# AY_Amp.net
KiCad netlist of a schematic drawn in Altium Designer
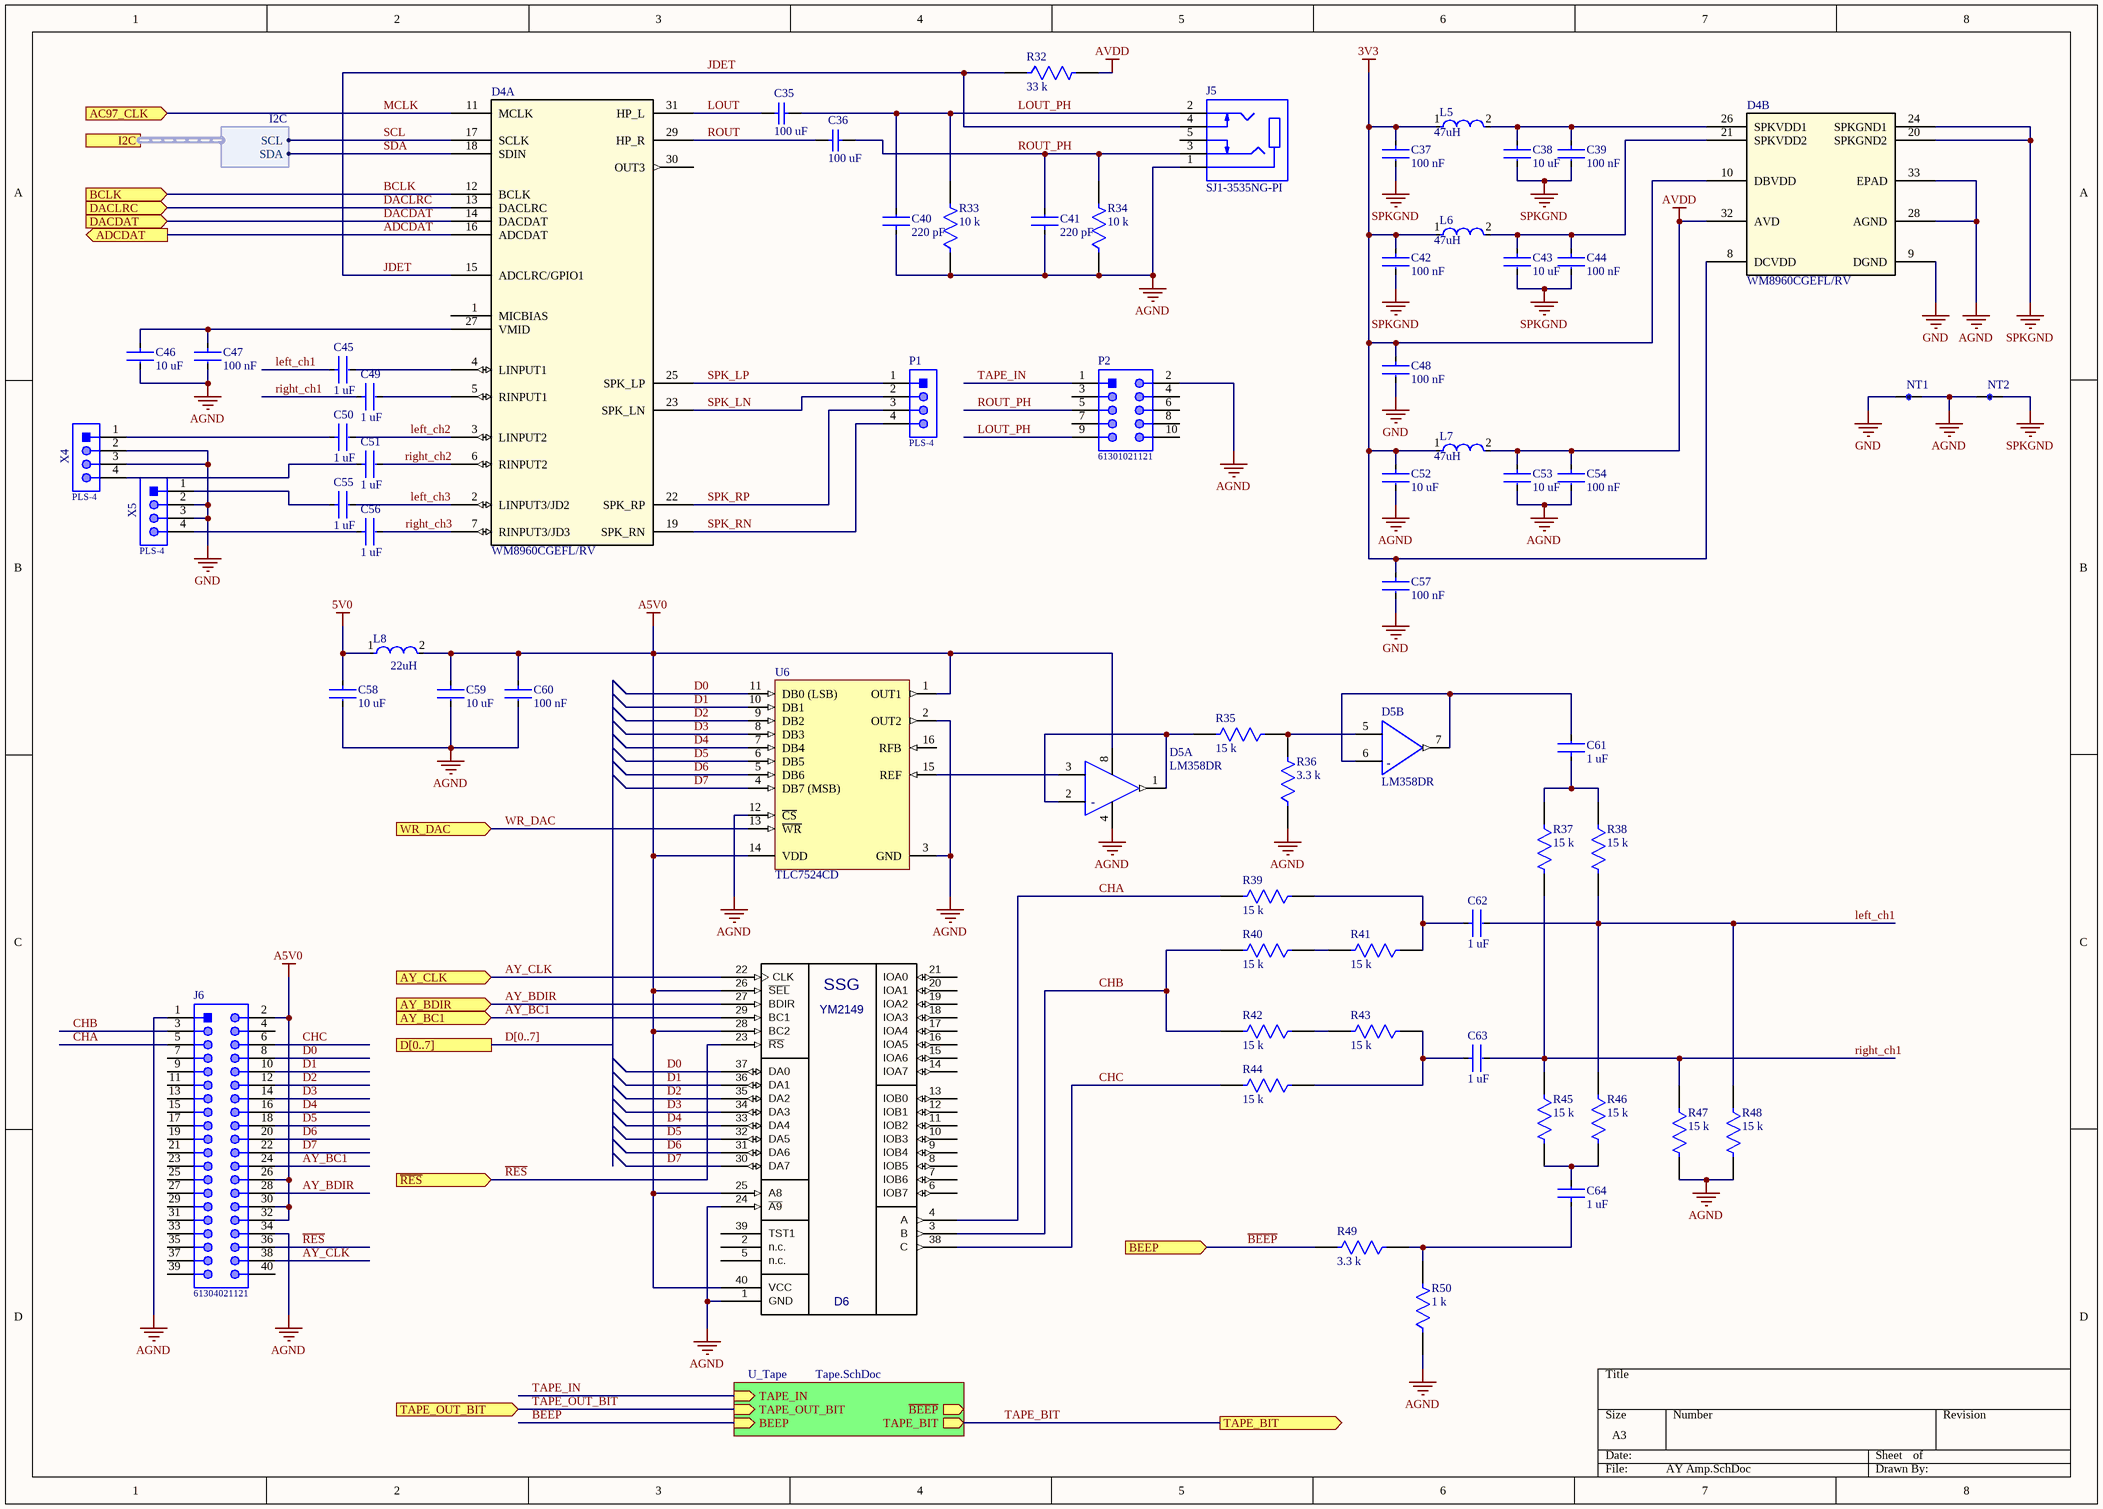
[diagram p0: AY Amp.SchDoc]

(export (version "E")
  (design (tool "Eeschema 10.0.6"))
  (components
    (comp (ref "C35")
      (value "CC1206-100uF")
      (footprint "CAPC3216X190X55ML30T25")
      (description "Chip Capacitor, 100 uF, +/- 20%, 6.3 V, -55 to 85 degC, 1206 (3216 Metric), RoHS, Tape and Reel")
      (fields
        (field (name "CAPACITANCE") "100 uF")
        (field (name "PARTNUMBER") "GRM31CR60J107ME39L")
        (field (name "MANUFACTURER") "Murata")
      )
      (libsource (lib "zxevo") (part "CMP-1662-00011-2"))
    )
    (comp (ref "C36")
      (value "CC1206-100uF")
      (footprint "CAPC3216X190X55ML30T25")
      (description "Chip Capacitor, 100 uF, +/- 20%, 6.3 V, -55 to 85 degC, 1206 (3216 Metric), RoHS, Tape and Reel")
      (fields
        (field (name "CAPACITANCE") "100 uF")
        (field (name "PARTNUMBER") "GRM31CR60J107ME39L")
        (field (name "MANUFACTURER") "Murata")
      )
      (libsource (lib "zxevo") (part "CMP-1662-00011-2"))
    )
    (comp (ref "C37")
      (value "CC0805-1.5pF")
      (footprint "CC0805")
      (description "CL21 Series 0805 1.5pF 50V ±0.25pF Tolerance C0G Multilayer Ceramic Chip Capacitor")
      (fields
        (field (name "MANUFACTURER PART NUMBER") "CL21C1R5CBANNNC")
        (field (name "MANUFACTURER") "Samsung")
        (field (name "CAPACITANCE") "100 nF")
      )
      (libsource (lib "zxevo") (part "CC0805"))
    )
    (comp (ref "C38")
      (value "CC0805-1.5pF")
      (footprint "CC0805")
      (description "CL21 Series 0805 1.5pF 50V ±0.25pF Tolerance C0G Multilayer Ceramic Chip Capacitor")
      (fields
        (field (name "MANUFACTURER PART NUMBER") "CL21C1R5CBANNNC")
        (field (name "MANUFACTURER") "Samsung")
        (field (name "CAPACITANCE") "10 uF")
      )
      (libsource (lib "zxevo") (part "CC0805"))
    )
    (comp (ref "C39")
      (value "CC0805-1.5pF")
      (footprint "CC0805")
      (description "CL21 Series 0805 1.5pF 50V ±0.25pF Tolerance C0G Multilayer Ceramic Chip Capacitor")
      (fields
        (field (name "MANUFACTURER PART NUMBER") "CL21C1R5CBANNNC")
        (field (name "MANUFACTURER") "Samsung")
        (field (name "CAPACITANCE") "100 nF")
      )
      (libsource (lib "zxevo") (part "CC0805"))
    )
    (comp (ref "C40")
      (value "CC0805-1.5pF")
      (footprint "CC0805")
      (description "CL21 Series 0805 1.5pF 50V ±0.25pF Tolerance C0G Multilayer Ceramic Chip Capacitor")
      (fields
        (field (name "MANUFACTURER PART NUMBER") "CL21C1R5CBANNNC")
        (field (name "CAPACITANCE") "220 pF")
        (field (name "MANUFACTURER") "Samsung")
      )
      (libsource (lib "zxevo") (part "CC0805"))
    )
    (comp (ref "C41")
      (value "CC0805-1.5pF")
      (footprint "CC0805")
      (description "CL21 Series 0805 1.5pF 50V ±0.25pF Tolerance C0G Multilayer Ceramic Chip Capacitor")
      (fields
        (field (name "MANUFACTURER PART NUMBER") "CL21C1R5CBANNNC")
        (field (name "CAPACITANCE") "220 pF")
        (field (name "MANUFACTURER") "Samsung")
      )
      (libsource (lib "zxevo") (part "CC0805"))
    )
    (comp (ref "C42")
      (value "CC0805-1.5pF")
      (footprint "CC0805")
      (description "CL21 Series 0805 1.5pF 50V ±0.25pF Tolerance C0G Multilayer Ceramic Chip Capacitor")
      (fields
        (field (name "MANUFACTURER PART NUMBER") "CL21C1R5CBANNNC")
        (field (name "MANUFACTURER") "Samsung")
        (field (name "CAPACITANCE") "100 nF")
      )
      (libsource (lib "zxevo") (part "CC0805"))
    )
    (comp (ref "C43")
      (value "CC0805-1.5pF")
      (footprint "CC0805")
      (description "CL21 Series 0805 1.5pF 50V ±0.25pF Tolerance C0G Multilayer Ceramic Chip Capacitor")
      (fields
        (field (name "MANUFACTURER PART NUMBER") "CL21C1R5CBANNNC")
        (field (name "MANUFACTURER") "Samsung")
        (field (name "CAPACITANCE") "10 uF")
      )
      (libsource (lib "zxevo") (part "CC0805"))
    )
    (comp (ref "C44")
      (value "CC0805-1.5pF")
      (footprint "CC0805")
      (description "CL21 Series 0805 1.5pF 50V ±0.25pF Tolerance C0G Multilayer Ceramic Chip Capacitor")
      (fields
        (field (name "MANUFACTURER PART NUMBER") "CL21C1R5CBANNNC")
        (field (name "MANUFACTURER") "Samsung")
        (field (name "CAPACITANCE") "100 nF")
      )
      (libsource (lib "zxevo") (part "CC0805"))
    )
    (comp (ref "C45")
      (value "CC0805-1.5pF")
      (footprint "CC0805")
      (description "CL21 Series 0805 1.5pF 50V ±0.25pF Tolerance C0G Multilayer Ceramic Chip Capacitor")
      (fields
        (field (name "CAPACITANCE") "1 uF")
        (field (name "MANUFACTURER") "Samsung")
        (field (name "MANUFACTURER PART NUMBER") "CL21C1R5CBANNNC")
      )
      (libsource (lib "zxevo") (part "CC0805"))
    )
    (comp (ref "C46")
      (value "CC0805-1.5pF")
      (footprint "CC0805")
      (description "CL21 Series 0805 1.5pF 50V ±0.25pF Tolerance C0G Multilayer Ceramic Chip Capacitor")
      (fields
        (field (name "MANUFACTURER PART NUMBER") "CL21C1R5CBANNNC")
        (field (name "MANUFACTURER") "Samsung")
        (field (name "CAPACITANCE") "10 uF")
      )
      (libsource (lib "zxevo") (part "CC0805"))
    )
    (comp (ref "C47")
      (value "CC0805-1.5pF")
      (footprint "CC0805")
      (description "CL21 Series 0805 1.5pF 50V ±0.25pF Tolerance C0G Multilayer Ceramic Chip Capacitor")
      (fields
        (field (name "MANUFACTURER PART NUMBER") "CL21C1R5CBANNNC")
        (field (name "MANUFACTURER") "Samsung")
        (field (name "CAPACITANCE") "100 nF")
      )
      (libsource (lib "zxevo") (part "CC0805"))
    )
    (comp (ref "C48")
      (value "CC0805-1.5pF")
      (footprint "CC0805")
      (description "CL21 Series 0805 1.5pF 50V ±0.25pF Tolerance C0G Multilayer Ceramic Chip Capacitor")
      (fields
        (field (name "MANUFACTURER PART NUMBER") "CL21C1R5CBANNNC")
        (field (name "MANUFACTURER") "Samsung")
        (field (name "CAPACITANCE") "100 nF")
      )
      (libsource (lib "zxevo") (part "CC0805"))
    )
    (comp (ref "C49")
      (value "CC0805-1.5pF")
      (footprint "CC0805")
      (description "CL21 Series 0805 1.5pF 50V ±0.25pF Tolerance C0G Multilayer Ceramic Chip Capacitor")
      (fields
        (field (name "CAPACITANCE") "1 uF")
        (field (name "MANUFACTURER") "Samsung")
        (field (name "MANUFACTURER PART NUMBER") "CL21C1R5CBANNNC")
      )
      (libsource (lib "zxevo") (part "CC0805"))
    )
    (comp (ref "C50")
      (value "CC0805-1.5pF")
      (footprint "CC0805")
      (description "CL21 Series 0805 1.5pF 50V ±0.25pF Tolerance C0G Multilayer Ceramic Chip Capacitor")
      (fields
        (field (name "CAPACITANCE") "1 uF")
        (field (name "MANUFACTURER") "Samsung")
        (field (name "MANUFACTURER PART NUMBER") "CL21C1R5CBANNNC")
      )
      (libsource (lib "zxevo") (part "CC0805"))
    )
    (comp (ref "C51")
      (value "CC0805-1.5pF")
      (footprint "CC0805")
      (description "CL21 Series 0805 1.5pF 50V ±0.25pF Tolerance C0G Multilayer Ceramic Chip Capacitor")
      (fields
        (field (name "CAPACITANCE") "1 uF")
        (field (name "MANUFACTURER") "Samsung")
        (field (name "MANUFACTURER PART NUMBER") "CL21C1R5CBANNNC")
      )
      (libsource (lib "zxevo") (part "CC0805"))
    )
    (comp (ref "C52")
      (value "CC0805-1.5pF")
      (footprint "CC0805")
      (description "CL21 Series 0805 1.5pF 50V ±0.25pF Tolerance C0G Multilayer Ceramic Chip Capacitor")
      (fields
        (field (name "MANUFACTURER PART NUMBER") "CL21C1R5CBANNNC")
        (field (name "MANUFACTURER") "Samsung")
        (field (name "CAPACITANCE") "10 uF")
      )
      (libsource (lib "zxevo") (part "CC0805"))
    )
    (comp (ref "C53")
      (value "CC0805-1.5pF")
      (footprint "CC0805")
      (description "CL21 Series 0805 1.5pF 50V ±0.25pF Tolerance C0G Multilayer Ceramic Chip Capacitor")
      (fields
        (field (name "MANUFACTURER PART NUMBER") "CL21C1R5CBANNNC")
        (field (name "MANUFACTURER") "Samsung")
        (field (name "CAPACITANCE") "10 uF")
      )
      (libsource (lib "zxevo") (part "CC0805"))
    )
    (comp (ref "C54")
      (value "CC0805-1.5pF")
      (footprint "CC0805")
      (description "CL21 Series 0805 1.5pF 50V ±0.25pF Tolerance C0G Multilayer Ceramic Chip Capacitor")
      (fields
        (field (name "MANUFACTURER PART NUMBER") "CL21C1R5CBANNNC")
        (field (name "MANUFACTURER") "Samsung")
        (field (name "CAPACITANCE") "100 nF")
      )
      (libsource (lib "zxevo") (part "CC0805"))
    )
    (comp (ref "C55")
      (value "CC0805-1.5pF")
      (footprint "CC0805")
      (description "CL21 Series 0805 1.5pF 50V ±0.25pF Tolerance C0G Multilayer Ceramic Chip Capacitor")
      (fields
        (field (name "CAPACITANCE") "1 uF")
        (field (name "MANUFACTURER") "Samsung")
        (field (name "MANUFACTURER PART NUMBER") "CL21C1R5CBANNNC")
      )
      (libsource (lib "zxevo") (part "CC0805"))
    )
    (comp (ref "C56")
      (value "CC0805-1.5pF")
      (footprint "CC0805")
      (description "CL21 Series 0805 1.5pF 50V ±0.25pF Tolerance C0G Multilayer Ceramic Chip Capacitor")
      (fields
        (field (name "CAPACITANCE") "1 uF")
        (field (name "MANUFACTURER") "Samsung")
        (field (name "MANUFACTURER PART NUMBER") "CL21C1R5CBANNNC")
      )
      (libsource (lib "zxevo") (part "CC0805"))
    )
    (comp (ref "C57")
      (value "CC0805-1.5pF")
      (footprint "CC0805")
      (description "CL21 Series 0805 1.5pF 50V ±0.25pF Tolerance C0G Multilayer Ceramic Chip Capacitor")
      (fields
        (field (name "MANUFACTURER PART NUMBER") "CL21C1R5CBANNNC")
        (field (name "MANUFACTURER") "Samsung")
        (field (name "CAPACITANCE") "100 nF")
      )
      (libsource (lib "zxevo") (part "CC0805"))
    )
    (comp (ref "C58")
      (value "CC0805-1.5pF")
      (footprint "CC0805")
      (description "CL21 Series 0805 1.5pF 50V ±0.25pF Tolerance C0G Multilayer Ceramic Chip Capacitor")
      (fields
        (field (name "MANUFACTURER PART NUMBER") "CL21C1R5CBANNNC")
        (field (name "MANUFACTURER") "Samsung")
        (field (name "CAPACITANCE") "10 uF")
      )
      (libsource (lib "zxevo") (part "CC0805"))
    )
    (comp (ref "C59")
      (value "CC0805-1.5pF")
      (footprint "CC0805")
      (description "CL21 Series 0805 1.5pF 50V ±0.25pF Tolerance C0G Multilayer Ceramic Chip Capacitor")
      (fields
        (field (name "MANUFACTURER PART NUMBER") "CL21C1R5CBANNNC")
        (field (name "MANUFACTURER") "Samsung")
        (field (name "CAPACITANCE") "10 uF")
      )
      (libsource (lib "zxevo") (part "CC0805"))
    )
    (comp (ref "C60")
      (value "CC0805-1.5pF")
      (footprint "CC0805")
      (description "CL21 Series 0805 1.5pF 50V ±0.25pF Tolerance C0G Multilayer Ceramic Chip Capacitor")
      (fields
        (field (name "MANUFACTURER PART NUMBER") "CL21C1R5CBANNNC")
        (field (name "MANUFACTURER") "Samsung")
        (field (name "CAPACITANCE") "100 nF")
      )
      (libsource (lib "zxevo") (part "CC0805"))
    )
    (comp (ref "C61")
      (value "CC0805-1.5pF")
      (footprint "CC0805")
      (description "CL21 Series 0805 1.5pF 50V ±0.25pF Tolerance C0G Multilayer Ceramic Chip Capacitor")
      (fields
        (field (name "CAPACITANCE") "1 uF")
        (field (name "MANUFACTURER") "Samsung")
        (field (name "MANUFACTURER PART NUMBER") "CL21C1R5CBANNNC")
      )
      (libsource (lib "zxevo") (part "CC0805"))
    )
    (comp (ref "C62")
      (value "CC0805-1.5pF")
      (footprint "CC0805")
      (description "CL21 Series 0805 1.5pF 50V ±0.25pF Tolerance C0G Multilayer Ceramic Chip Capacitor")
      (fields
        (field (name "CAPACITANCE") "1 uF")
        (field (name "MANUFACTURER") "Samsung")
        (field (name "MANUFACTURER PART NUMBER") "CL21C1R5CBANNNC")
      )
      (libsource (lib "zxevo") (part "CC0805"))
    )
    (comp (ref "C63")
      (value "CC0805-1.5pF")
      (footprint "CC0805")
      (description "CL21 Series 0805 1.5pF 50V ±0.25pF Tolerance C0G Multilayer Ceramic Chip Capacitor")
      (fields
        (field (name "CAPACITANCE") "1 uF")
        (field (name "MANUFACTURER") "Samsung")
        (field (name "MANUFACTURER PART NUMBER") "CL21C1R5CBANNNC")
      )
      (libsource (lib "zxevo") (part "CC0805"))
    )
    (comp (ref "C64")
      (value "CC0805-1.5pF")
      (footprint "CC0805")
      (description "CL21 Series 0805 1.5pF 50V ±0.25pF Tolerance C0G Multilayer Ceramic Chip Capacitor")
      (fields
        (field (name "CAPACITANCE") "1 uF")
        (field (name "MANUFACTURER") "Samsung")
        (field (name "MANUFACTURER PART NUMBER") "CL21C1R5CBANNNC")
      )
      (libsource (lib "zxevo") (part "CC0805"))
    )
    (comp (ref "D4")
      (value "WM8960CGEFL/RV")
      (footprint "QFN50P500X500X90_HS-33M")
      (description "Stereo CODEC with 1W Stereo Class-D speaker Drivers")
      (libsource (lib "zxevo") (part "WM8960CGEFL/RV"))
    )
    (comp (ref "D5")
      (value "LM358DR")
      (footprint "FP-D0008A-MFG")
      (description "IC OPAMP GP 2 CIRCUIT 8SOIC")
      (fields (field (name "MANUFACTURER") "Texas Instruments"))
      (libsource (lib "zxevo") (part "LM358DR"))
    )
    (comp (ref "D6") (value "YM2149") (footprint "DIP40") (libsource (lib "zxevo") (part "YM2149")))
    (comp (ref "J5")
      (value "SJ1-3535NG-PI")
      (footprint "CUI_SJ1-3535NG-PI")
      (description "3.5 mm Right-Angle Stereo Jack, 5 pin PCB PCB Mount, Isolated Ground, Pink")
      (fields (field (name "MF") "{'manufacturer': u'CUI'}"))
      (libsource (lib "zxevo") (part "SJ1-3535NG-PI"))
    )
    (comp (ref "J6")
      (value "61304021121")
      (footprint "61304021121")
      (description "THT Vertical Pin Header WR-PHD, Pitch 2.54 mm, Dual Row, 40 pins")
      (fields (field (name "MANUFACTURER") "Wurth Elektronik") (field (name "PUBLISHER") "WurthElektronik"))
      (libsource (lib "Altium Content Vault") (part "WE-CN-2P-M-R40"))
    )
    (comp (ref "L5")
      (value "NR6028T470M")
      (footprint "FP-NR6028-MFG")
      (description "SMD Power Inductors 47uH ±20% 0.92A 0.39Ω")
      (fields (field (name "INDUCTANCE") "47uH") (field (name "TOLERANCE") "20%"))
      (libsource (lib "Altium Content Vault") (part "725321dda6339637d4d059423bc1c3c"))
    )
    (comp (ref "L6")
      (value "NR6028T470M")
      (footprint "FP-NR6028-MFG")
      (description "SMD Power Inductors 47uH ±20% 0.92A 0.39Ω")
      (fields (field (name "INDUCTANCE") "47uH") (field (name "TOLERANCE") "20%"))
      (libsource (lib "Altium Content Vault") (part "725321dda6339637d4d059423bc1c3c"))
    )
    (comp (ref "L7")
      (value "NR6028T470M")
      (footprint "FP-NR6028-MFG")
      (description "SMD Power Inductors 47uH ±20% 0.92A 0.39Ω")
      (fields (field (name "INDUCTANCE") "47uH") (field (name "TOLERANCE") "20%"))
      (libsource (lib "Altium Content Vault") (part "725321dda6339637d4d059423bc1c3c"))
    )
    (comp (ref "L8")
      (value "LQH43CN220K03L")
      (footprint "FP-LQH43CN_03-MFG")
      (description "Wire Wound Ferrite Inductor for Power Lines 22μH ±10% 0.6Ω 420mA 1812")
      (fields
        (field (name "INDUCTANCE") "22uH")
        (field (name "TOLERANCE") "10%")
        (field (name "MANUFACTURER") "Murata")
      )
      (libsource (lib "zxevo") (part "CMP-06042-007646-1"))
    )
    (comp (ref "NT1") (value "net_tie") (footprint "NET_TIE") (libsource (lib "zxevo") (part "net_tie")))
    (comp (ref "NT2") (value "net_tie") (footprint "NET_TIE") (libsource (lib "zxevo") (part "net_tie")))
    (comp (ref "P1")
      (value "PLS-4")
      (footprint "61300411121")
      (description "THT Vertical Pin Header WR-PHD, Pitch 2.54 mm, Single Row, 4 pins")
      (fields
        (field (name "MANUFACTURER") "Wurth Electronics")
        (field (name "MANUFACTURER PART NUMBER") "61300411121")
      )
      (libsource (lib "zxevo") (part "PLS-4"))
    )
    (comp (ref "P2")
      (value "61301021121")
      (footprint "61301021121")
      (description "THT Vertical Pin Header WR-PHD, Pitch 2.54 mm, Dual Row, 10 pins")
      (fields (field (name "MANUFACTURER") "Wurth Elektronik") (field (name "PUBLISHER") "WurthElektronik"))
      (libsource (lib "Altium Content Vault") (part "WE-CN-2P-M-R10"))
    )
    (comp (ref "R32")
      (value "CR0805-51")
      (footprint "CR0805")
      (description "51Ω ±0.5% 0.1W 1/10W Chip Resistor 0805 (2012 Metric) Thin Film")
      (fields
        (field (name "RESISTANCE") "33 k")
        (field (name "MANUFACTURER") "Susumu")
        (field (name "MANUFACTURER PART NUMBER") "RR1220Q-510-D")
      )
      (libsource (lib "zxevo") (part "CR0805"))
    )
    (comp (ref "R33")
      (value "CR0805-51")
      (footprint "CR0805")
      (description "51Ω ±0.5% 0.1W 1/10W Chip Resistor 0805 (2012 Metric) Thin Film")
      (fields
        (field (name "RESISTANCE") "10 k")
        (field (name "MANUFACTURER") "Susumu")
        (field (name "MANUFACTURER PART NUMBER") "RR1220Q-510-D")
      )
      (libsource (lib "zxevo") (part "CR0805"))
    )
    (comp (ref "R34")
      (value "CR0805-51")
      (footprint "CR0805")
      (description "51Ω ±0.5% 0.1W 1/10W Chip Resistor 0805 (2012 Metric) Thin Film")
      (fields
        (field (name "RESISTANCE") "10 k")
        (field (name "MANUFACTURER") "Susumu")
        (field (name "MANUFACTURER PART NUMBER") "RR1220Q-510-D")
      )
      (libsource (lib "zxevo") (part "CR0805"))
    )
    (comp (ref "R35")
      (value "CR0805-51")
      (footprint "CR0805")
      (description "51Ω ±0.5% 0.1W 1/10W Chip Resistor 0805 (2012 Metric) Thin Film")
      (fields
        (field (name "MANUFACTURER PART NUMBER") "RR1220Q-510-D")
        (field (name "MANUFACTURER") "Susumu")
        (field (name "RESISTANCE") "15 k")
      )
      (libsource (lib "zxevo") (part "CR0805"))
    )
    (comp (ref "R36")
      (value "CR0805-51")
      (footprint "CR0805")
      (description "51Ω ±0.5% 0.1W 1/10W Chip Resistor 0805 (2012 Metric) Thin Film")
      (fields
        (field (name "MANUFACTURER PART NUMBER") "RR1220Q-510-D")
        (field (name "MANUFACTURER") "Susumu")
        (field (name "RESISTANCE") "3.3 k")
      )
      (libsource (lib "zxevo") (part "CR0805"))
    )
    (comp (ref "R37")
      (value "CR0805-51")
      (footprint "CR0805")
      (description "51Ω ±0.5% 0.1W 1/10W Chip Resistor 0805 (2012 Metric) Thin Film")
      (fields
        (field (name "MANUFACTURER PART NUMBER") "RR1220Q-510-D")
        (field (name "MANUFACTURER") "Susumu")
        (field (name "RESISTANCE") "15 k")
      )
      (libsource (lib "zxevo") (part "CR0805"))
    )
    (comp (ref "R38")
      (value "CR0805-51")
      (footprint "CR0805")
      (description "51Ω ±0.5% 0.1W 1/10W Chip Resistor 0805 (2012 Metric) Thin Film")
      (fields
        (field (name "MANUFACTURER PART NUMBER") "RR1220Q-510-D")
        (field (name "MANUFACTURER") "Susumu")
        (field (name "RESISTANCE") "15 k")
      )
      (libsource (lib "zxevo") (part "CR0805"))
    )
    (comp (ref "R39")
      (value "CR0805-51")
      (footprint "CR0805")
      (description "51Ω ±0.5% 0.1W 1/10W Chip Resistor 0805 (2012 Metric) Thin Film")
      (fields
        (field (name "MANUFACTURER PART NUMBER") "RR1220Q-510-D")
        (field (name "MANUFACTURER") "Susumu")
        (field (name "RESISTANCE") "15 k")
      )
      (libsource (lib "zxevo") (part "CR0805"))
    )
    (comp (ref "R40")
      (value "CR0805-51")
      (footprint "CR0805")
      (description "51Ω ±0.5% 0.1W 1/10W Chip Resistor 0805 (2012 Metric) Thin Film")
      (fields
        (field (name "MANUFACTURER PART NUMBER") "RR1220Q-510-D")
        (field (name "MANUFACTURER") "Susumu")
        (field (name "RESISTANCE") "15 k")
      )
      (libsource (lib "zxevo") (part "CR0805"))
    )
    (comp (ref "R41")
      (value "CR0805-51")
      (footprint "CR0805")
      (description "51Ω ±0.5% 0.1W 1/10W Chip Resistor 0805 (2012 Metric) Thin Film")
      (fields
        (field (name "MANUFACTURER PART NUMBER") "RR1220Q-510-D")
        (field (name "MANUFACTURER") "Susumu")
        (field (name "RESISTANCE") "15 k")
      )
      (libsource (lib "zxevo") (part "CR0805"))
    )
    (comp (ref "R42")
      (value "CR0805-51")
      (footprint "CR0805")
      (description "51Ω ±0.5% 0.1W 1/10W Chip Resistor 0805 (2012 Metric) Thin Film")
      (fields
        (field (name "MANUFACTURER PART NUMBER") "RR1220Q-510-D")
        (field (name "MANUFACTURER") "Susumu")
        (field (name "RESISTANCE") "15 k")
      )
      (libsource (lib "zxevo") (part "CR0805"))
    )
    (comp (ref "R43")
      (value "CR0805-51")
      (footprint "CR0805")
      (description "51Ω ±0.5% 0.1W 1/10W Chip Resistor 0805 (2012 Metric) Thin Film")
      (fields
        (field (name "MANUFACTURER PART NUMBER") "RR1220Q-510-D")
        (field (name "MANUFACTURER") "Susumu")
        (field (name "RESISTANCE") "15 k")
      )
      (libsource (lib "zxevo") (part "CR0805"))
    )
    (comp (ref "R44")
      (value "CR0805-51")
      (footprint "CR0805")
      (description "51Ω ±0.5% 0.1W 1/10W Chip Resistor 0805 (2012 Metric) Thin Film")
      (fields
        (field (name "MANUFACTURER PART NUMBER") "RR1220Q-510-D")
        (field (name "MANUFACTURER") "Susumu")
        (field (name "RESISTANCE") "15 k")
      )
      (libsource (lib "zxevo") (part "CR0805"))
    )
    (comp (ref "R45")
      (value "CR0805-51")
      (footprint "CR0805")
      (description "51Ω ±0.5% 0.1W 1/10W Chip Resistor 0805 (2012 Metric) Thin Film")
      (fields
        (field (name "MANUFACTURER PART NUMBER") "RR1220Q-510-D")
        (field (name "MANUFACTURER") "Susumu")
        (field (name "RESISTANCE") "15 k")
      )
      (libsource (lib "zxevo") (part "CR0805"))
    )
    (comp (ref "R46")
      (value "CR0805-51")
      (footprint "CR0805")
      (description "51Ω ±0.5% 0.1W 1/10W Chip Resistor 0805 (2012 Metric) Thin Film")
      (fields
        (field (name "MANUFACTURER PART NUMBER") "RR1220Q-510-D")
        (field (name "MANUFACTURER") "Susumu")
        (field (name "RESISTANCE") "15 k")
      )
      (libsource (lib "zxevo") (part "CR0805"))
    )
    (comp (ref "R47")
      (value "CR0805-51")
      (footprint "CR0805")
      (description "51Ω ±0.5% 0.1W 1/10W Chip Resistor 0805 (2012 Metric) Thin Film")
      (fields
        (field (name "MANUFACTURER PART NUMBER") "RR1220Q-510-D")
        (field (name "MANUFACTURER") "Susumu")
        (field (name "RESISTANCE") "15 k")
      )
      (libsource (lib "zxevo") (part "CR0805"))
    )
    (comp (ref "R48")
      (value "CR0805-51")
      (footprint "CR0805")
      (description "51Ω ±0.5% 0.1W 1/10W Chip Resistor 0805 (2012 Metric) Thin Film")
      (fields
        (field (name "MANUFACTURER PART NUMBER") "RR1220Q-510-D")
        (field (name "MANUFACTURER") "Susumu")
        (field (name "RESISTANCE") "15 k")
      )
      (libsource (lib "zxevo") (part "CR0805"))
    )
    (comp (ref "R49")
      (value "CR0805-51")
      (footprint "CR0805")
      (description "51Ω ±0.5% 0.1W 1/10W Chip Resistor 0805 (2012 Metric) Thin Film")
      (fields
        (field (name "MANUFACTURER PART NUMBER") "RR1220Q-510-D")
        (field (name "MANUFACTURER") "Susumu")
        (field (name "RESISTANCE") "3.3 k")
      )
      (libsource (lib "zxevo") (part "CR0805"))
    )
    (comp (ref "R50")
      (value "CR0805-51")
      (footprint "CR0805")
      (description "51Ω ±0.5% 0.1W 1/10W Chip Resistor 0805 (2012 Metric) Thin Film")
      (fields
        (field (name "RESISTANCE") "1 k")
        (field (name "MANUFACTURER") "Susumu")
        (field (name "MANUFACTURER PART NUMBER") "RR1220Q-510-D")
      )
      (libsource (lib "zxevo") (part "CR0805"))
    )
    (comp (ref "U6")
      (value "TLC7524CD")
      (footprint "SO16W")
      (fields (field (name "MANUFACTURER") "Texas Instruments"))
      (libsource (lib "zxevo") (part "TLC7524CD"))
    )
    (comp (ref "X4")
      (value "PLS-4")
      (footprint "61300411121")
      (description "THT Vertical Pin Header WR-PHD, Pitch 2.54 mm, Single Row, 4 pins")
      (fields
        (field (name "MANUFACTURER") "Wurth Electronics")
        (field (name "MANUFACTURER PART NUMBER") "61300411121")
      )
      (libsource (lib "") (part "PLS-4_1"))
    )
    (comp (ref "X5")
      (value "PLS-4")
      (footprint "61300411121")
      (description "THT Vertical Pin Header WR-PHD, Pitch 2.54 mm, Single Row, 4 pins")
      (fields
        (field (name "MANUFACTURER") "Wurth Electronics")
        (field (name "MANUFACTURER PART NUMBER") "61300411121")
      )
      (libsource (lib "") (part "PLS-4_1"))
    )
  )
  (nets
    (net (code "2") (name "/ADCDAT") (class "Default")
      (node (ref "D4") (pin "16") (pinfunction "ADCDAT_16") (pintype "passive"))
    )
    (net (code "3") (name "/AY_BC1") (class "Default")
      (node (ref "D6") (pin "29") (pinfunction "BC1_29") (pintype "input"))
      (node (ref "J6") (pin "24") (pinfunction "24_24") (pintype "passive"))
    )
    (net (code "4") (name "/AY_BDIR") (class "Default")
      (node (ref "D6") (pin "27") (pinfunction "BDIR_27") (pintype "input"))
      (node (ref "J6") (pin "28") (pinfunction "28_28") (pintype "passive"))
    )
    (net (code "5") (name "/AY_CLK") (class "Default")
      (node (ref "D6") (pin "22") (pinfunction "CLK_22") (pintype "input"))
      (node (ref "J6") (pin "38") (pinfunction "38_38") (pintype "passive"))
    )
    (net (code "6") (name "/BCLK") (class "Default")
      (node (ref "D4") (pin "12") (pinfunction "BCLK_12") (pintype "passive"))
    )
    (net (code "7") (name "/BEEP") (class "Default")
      (node (ref "R49") (pin "2") (pinfunction "2_2") (pintype "passive"))
    )
    (net (code "8") (name "/CHA") (class "Default")
      (node (ref "D6") (pin "4") (pinfunction "A_4") (pintype "output"))
      (node (ref "J6") (pin "5") (pinfunction "5_5") (pintype "passive"))
      (node (ref "R39") (pin "2") (pinfunction "2_2") (pintype "passive"))
    )
    (net (code "9") (name "/CHB") (class "Default")
      (node (ref "D6") (pin "3") (pinfunction "B_3") (pintype "output"))
      (node (ref "J6") (pin "3") (pinfunction "3_3") (pintype "passive"))
      (node (ref "R40") (pin "2") (pinfunction "2_2") (pintype "passive"))
      (node (ref "R42") (pin "2") (pinfunction "2_2") (pintype "passive"))
    )
    (net (code "10") (name "/CHC") (class "Default")
      (node (ref "D6") (pin "38") (pinfunction "C_38") (pintype "output"))
      (node (ref "J6") (pin "6") (pinfunction "6_6") (pintype "passive"))
      (node (ref "R44") (pin "2") (pinfunction "2_2") (pintype "passive"))
    )
    (net (code "11") (name "/D0") (class "Default")
      (node (ref "D6") (pin "37") (pinfunction "DA0_37") (pintype "bidirectional"))
      (node (ref "J6") (pin "8") (pinfunction "8_8") (pintype "passive"))
      (node (ref "U6") (pin "11") (pinfunction "DB0_(LSB)_11") (pintype "input"))
    )
    (net (code "12") (name "/D1") (class "Default")
      (node (ref "D6") (pin "36") (pinfunction "DA1_36") (pintype "bidirectional"))
      (node (ref "J6") (pin "10") (pinfunction "10_10") (pintype "passive"))
      (node (ref "U6") (pin "10") (pinfunction "DB1_10") (pintype "input"))
    )
    (net (code "13") (name "/D2") (class "Default")
      (node (ref "D6") (pin "35") (pinfunction "DA2_35") (pintype "bidirectional"))
      (node (ref "J6") (pin "12") (pinfunction "12_12") (pintype "passive"))
      (node (ref "U6") (pin "9") (pinfunction "DB2_9") (pintype "input"))
    )
    (net (code "14") (name "/D3") (class "Default")
      (node (ref "D6") (pin "34") (pinfunction "DA3_34") (pintype "bidirectional"))
      (node (ref "J6") (pin "14") (pinfunction "14_14") (pintype "passive"))
      (node (ref "U6") (pin "8") (pinfunction "DB3_8") (pintype "input"))
    )
    (net (code "15") (name "/D4") (class "Default")
      (node (ref "D6") (pin "33") (pinfunction "DA4_33") (pintype "bidirectional"))
      (node (ref "J6") (pin "16") (pinfunction "16_16") (pintype "passive"))
      (node (ref "U6") (pin "7") (pinfunction "DB4_7") (pintype "input"))
    )
    (net (code "16") (name "/D5") (class "Default")
      (node (ref "D6") (pin "32") (pinfunction "DA5_32") (pintype "bidirectional"))
      (node (ref "J6") (pin "18") (pinfunction "18_18") (pintype "passive"))
      (node (ref "U6") (pin "6") (pinfunction "DB5_6") (pintype "input"))
    )
    (net (code "17") (name "/D6") (class "Default")
      (node (ref "D6") (pin "31") (pinfunction "DA6_31") (pintype "bidirectional"))
      (node (ref "J6") (pin "20") (pinfunction "20_20") (pintype "passive"))
      (node (ref "U6") (pin "5") (pinfunction "DB6_5") (pintype "input"))
    )
    (net (code "18") (name "/D7") (class "Default")
      (node (ref "D6") (pin "30") (pinfunction "DA7_30") (pintype "bidirectional"))
      (node (ref "J6") (pin "22") (pinfunction "22_22") (pintype "passive"))
      (node (ref "U6") (pin "4") (pinfunction "DB7_(MSB)_4") (pintype "input"))
    )
    (net (code "19") (name "/DACDAT") (class "Default")
      (node (ref "D4") (pin "14") (pinfunction "DACDAT_14") (pintype "passive"))
    )
    (net (code "20") (name "/DACLRC") (class "Default")
      (node (ref "D4") (pin "13") (pinfunction "DACLRC_13") (pintype "passive"))
    )
    (net (code "22") (name "/JDET") (class "Default")
      (node (ref "D4") (pin "15") (pinfunction "ADCLRC/GPIO1_15") (pintype "passive"))
      (node (ref "J5") (pin "4") (pinfunction "4_4") (pintype "passive"))
      (node (ref "R32") (pin "1") (pinfunction "1_1") (pintype "passive"))
    )
    (net (code "23") (name "/LOUT") (class "Default")
      (node (ref "C35") (pin "1") (pinfunction "1_1") (pintype "passive"))
      (node (ref "D4") (pin "31") (pinfunction "HP_L_31") (pintype "passive"))
    )
    (net (code "24") (name "/LOUT_PH") (class "Default")
      (node (ref "C35") (pin "2") (pinfunction "2_2") (pintype "passive"))
      (node (ref "C40") (pin "2") (pinfunction "2_2") (pintype "passive"))
      (node (ref "J5") (pin "2") (pinfunction "2_2") (pintype "passive"))
      (node (ref "P2") (pin "9") (pinfunction "9_9") (pintype "passive"))
      (node (ref "R33") (pin "2") (pinfunction "2_2") (pintype "passive"))
    )
    (net (code "25") (name "/MCLK") (class "Default")
      (node (ref "D4") (pin "11") (pinfunction "MCLK_11") (pintype "passive"))
    )
    (net (code "26") (name "/ROUT") (class "Default")
      (node (ref "C36") (pin "1") (pinfunction "1_1") (pintype "passive"))
      (node (ref "D4") (pin "29") (pinfunction "HP_R_29") (pintype "passive"))
    )
    (net (code "27") (name "/ROUT_PH") (class "Default")
      (node (ref "C36") (pin "2") (pinfunction "2_2") (pintype "passive"))
      (node (ref "C41") (pin "2") (pinfunction "2_2") (pintype "passive"))
      (node (ref "J5") (pin "3") (pinfunction "3_3") (pintype "passive"))
      (node (ref "P2") (pin "5") (pinfunction "5_5") (pintype "passive"))
      (node (ref "R34") (pin "2") (pinfunction "2_2") (pintype "passive"))
    )
    (net (code "28") (name "/SCL") (class "Default")
      (node (ref "D4") (pin "17") (pinfunction "SCLK_17") (pintype "passive"))
    )
    (net (code "29") (name "/SDA") (class "Default")
      (node (ref "D4") (pin "18") (pinfunction "SDIN_18") (pintype "passive"))
    )
    (net (code "30") (name "/SPK_LN") (class "Default")
      (node (ref "D4") (pin "23") (pinfunction "SPK_LN_23") (pintype "passive"))
      (node (ref "P1") (pin "2") (pinfunction "2_2") (pintype "passive"))
    )
    (net (code "31") (name "/SPK_LP") (class "Default")
      (node (ref "D4") (pin "25") (pinfunction "SPK_LP_25") (pintype "passive"))
      (node (ref "P1") (pin "1") (pinfunction "1_1") (pintype "passive"))
    )
    (net (code "32") (name "/SPK_RN") (class "Default")
      (node (ref "D4") (pin "19") (pinfunction "SPK_RN_19") (pintype "passive"))
      (node (ref "P1") (pin "4") (pinfunction "4_4") (pintype "passive"))
    )
    (net (code "33") (name "/SPK_RP") (class "Default")
      (node (ref "D4") (pin "22") (pinfunction "SPK_RP_22") (pintype "passive"))
      (node (ref "P1") (pin "3") (pinfunction "3_3") (pintype "passive"))
    )
    (net (code "35") (name "/TAPE_IN") (class "Default")
      (node (ref "P2") (pin "1") (pinfunction "1_1") (pintype "passive"))
    )
    (net (code "37") (name "/WR_DAC") (class "Default")
      (node (ref "U6") (pin "13") (pinfunction "~{WR}_13") (pintype "input"))
    )
    (net (code "38") (name "/left_ch1") (class "Default")
      (node (ref "C45") (pin "1") (pinfunction "1_1") (pintype "passive"))
      (node (ref "C62") (pin "2") (pinfunction "2_2") (pintype "passive"))
      (node (ref "R38") (pin "2") (pinfunction "2_2") (pintype "passive"))
      (node (ref "R46") (pin "1") (pinfunction "1_1") (pintype "passive"))
      (node (ref "R48") (pin "1") (pinfunction "1_1") (pintype "passive"))
    )
    (net (code "39") (name "/left_ch2") (class "Default")
      (node (ref "C50") (pin "2") (pinfunction "2_2") (pintype "passive"))
      (node (ref "D4") (pin "3") (pinfunction "LINPUT2_3") (pintype "bidirectional"))
    )
    (net (code "40") (name "/left_ch3") (class "Default")
      (node (ref "C55") (pin "2") (pinfunction "2_2") (pintype "passive"))
      (node (ref "D4") (pin "2") (pinfunction "LINPUT3/JD2_2") (pintype "bidirectional"))
    )
    (net (code "41") (name "/right_ch1") (class "Default")
      (node (ref "C49") (pin "1") (pinfunction "1_1") (pintype "passive"))
      (node (ref "C63") (pin "2") (pinfunction "2_2") (pintype "passive"))
      (node (ref "R37") (pin "2") (pinfunction "2_2") (pintype "passive"))
      (node (ref "R45") (pin "1") (pinfunction "1_1") (pintype "passive"))
      (node (ref "R47") (pin "1") (pinfunction "1_1") (pintype "passive"))
    )
    (net (code "42") (name "/right_ch2") (class "Default")
      (node (ref "C51") (pin "2") (pinfunction "2_2") (pintype "passive"))
      (node (ref "D4") (pin "6") (pinfunction "RINPUT2_6") (pintype "bidirectional"))
    )
    (net (code "43") (name "/right_ch3") (class "Default")
      (node (ref "C56") (pin "2") (pinfunction "2_2") (pintype "passive"))
      (node (ref "D4") (pin "7") (pinfunction "RINPUT3/JD3_7") (pintype "bidirectional"))
    )
    (net (code "46") (name "/~{RES}") (class "Default")
      (node (ref "D6") (pin "23") (pinfunction "~{RS}_23") (pintype "input"))
      (node (ref "J6") (pin "36") (pinfunction "36_36") (pintype "passive"))
    )
    (net (code "47") (name "3V3") (class "Default")
      (node (ref "C37") (pin "1") (pinfunction "1_1") (pintype "passive"))
      (node (ref "C42") (pin "1") (pinfunction "1_1") (pintype "passive"))
      (node (ref "C48") (pin "1") (pinfunction "1_1") (pintype "passive"))
      (node (ref "C52") (pin "1") (pinfunction "1_1") (pintype "passive"))
      (node (ref "C57") (pin "1") (pinfunction "1_1") (pintype "passive"))
      (node (ref "D4") (pin "10") (pinfunction "DBVDD_10") (pintype "power_in"))
      (node (ref "D4") (pin "8") (pinfunction "DCVDD_8") (pintype "power_in"))
      (node (ref "L5") (pin "1") (pinfunction "1_1") (pintype "passive"))
      (node (ref "L6") (pin "1") (pinfunction "1_1") (pintype "passive"))
      (node (ref "L7") (pin "1") (pinfunction "1_1") (pintype "passive"))
    )
    (net (code "48") (name "5V0") (class "Default")
      (node (ref "C58") (pin "1") (pinfunction "1_1") (pintype "passive"))
      (node (ref "L8") (pin "1") (pinfunction "1_1") (pintype "passive"))
    )
    (net (code "49") (name "A5V0") (class "Default")
      (node (ref "C59") (pin "1") (pinfunction "1_1") (pintype "passive"))
      (node (ref "C60") (pin "1") (pinfunction "1_1") (pintype "passive"))
      (node (ref "D5") (pin "8") (pinfunction "V+_8") (pintype "power_in"))
      (node (ref "D6") (pin "25") (pinfunction "A8_25") (pintype "input"))
      (node (ref "D6") (pin "26") (pinfunction "~{SEL}_26") (pintype "input"))
      (node (ref "D6") (pin "28") (pinfunction "BC2_28") (pintype "input"))
      (node (ref "D6") (pin "40") (pinfunction "VCC_40") (pintype "power_in"))
      (node (ref "J6") (pin "2") (pinfunction "2_2") (pintype "passive"))
      (node (ref "J6") (pin "26") (pinfunction "26_26") (pintype "passive"))
      (node (ref "J6") (pin "30") (pinfunction "30_30") (pintype "passive"))
      (node (ref "J6") (pin "32") (pinfunction "32_32") (pintype "passive"))
      (node (ref "L8") (pin "2") (pinfunction "2_2") (pintype "passive"))
      (node (ref "U6") (pin "1") (pinfunction "OUT1_1") (pintype "output"))
      (node (ref "U6") (pin "14") (pinfunction "VDD_14") (pintype "power_in"))
    )
    (net (code "50") (name "AGND") (class "Default")
      (node (ref "C40") (pin "1") (pinfunction "1_1") (pintype "passive"))
      (node (ref "C41") (pin "1") (pinfunction "1_1") (pintype "passive"))
      (node (ref "C46") (pin "2") (pinfunction "2_2") (pintype "passive"))
      (node (ref "C47") (pin "2") (pinfunction "2_2") (pintype "passive"))
      (node (ref "C52") (pin "2") (pinfunction "2_2") (pintype "passive"))
      (node (ref "C53") (pin "2") (pinfunction "2_2") (pintype "passive"))
      (node (ref "C54") (pin "2") (pinfunction "2_2") (pintype "passive"))
      (node (ref "C58") (pin "2") (pinfunction "2_2") (pintype "passive"))
      (node (ref "C59") (pin "2") (pinfunction "2_2") (pintype "passive"))
      (node (ref "C60") (pin "2") (pinfunction "2_2") (pintype "passive"))
      (node (ref "D4") (pin "28") (pinfunction "AGND_28") (pintype "passive"))
      (node (ref "D4") (pin "33") (pinfunction "EPAD_33") (pintype "passive"))
      (node (ref "D5") (pin "4") (pinfunction "V-_4") (pintype "power_in"))
      (node (ref "D6") (pin "1") (pinfunction "GND_1") (pintype "power_in"))
      (node (ref "D6") (pin "24") (pinfunction "~{A9}_24") (pintype "input"))
      (node (ref "J5") (pin "1") (pinfunction "1_1") (pintype "passive"))
      (node (ref "J6") (pin "1") (pinfunction "1_1") (pintype "passive"))
      (node (ref "J6") (pin "34") (pinfunction "34_34") (pintype "passive"))
      (node (ref "NT1") (pin "2") (pintype "passive"))
      (node (ref "NT2") (pin "1") (pintype "passive"))
      (node (ref "P2") (pin "2") (pinfunction "2_2") (pintype "passive"))
      (node (ref "R33") (pin "1") (pinfunction "1_1") (pintype "passive"))
      (node (ref "R34") (pin "1") (pinfunction "1_1") (pintype "passive"))
      (node (ref "R36") (pin "1") (pinfunction "1_1") (pintype "passive"))
      (node (ref "R47") (pin "2") (pinfunction "2_2") (pintype "passive"))
      (node (ref "R48") (pin "2") (pinfunction "2_2") (pintype "passive"))
      (node (ref "R50") (pin "1") (pinfunction "1_1") (pintype "passive"))
      (node (ref "U6") (pin "12") (pinfunction "~{CS}_12") (pintype "input"))
      (node (ref "U6") (pin "2") (pinfunction "OUT2_2") (pintype "output"))
      (node (ref "U6") (pin "3") (pinfunction "GND_3") (pintype "power_in"))
    )
    (net (code "51") (name "AVDD") (class "Default")
      (node (ref "C53") (pin "1") (pinfunction "1_1") (pintype "passive"))
      (node (ref "C54") (pin "1") (pinfunction "1_1") (pintype "passive"))
      (node (ref "D4") (pin "32") (pinfunction "AVD_32") (pintype "passive"))
      (node (ref "L7") (pin "2") (pinfunction "2_2") (pintype "passive"))
      (node (ref "R32") (pin "2") (pinfunction "2_2") (pintype "passive"))
    )
    (net (code "52") (name "GND") (class "Default")
      (node (ref "C48") (pin "2") (pinfunction "2_2") (pintype "passive"))
      (node (ref "C57") (pin "2") (pinfunction "2_2") (pintype "passive"))
      (node (ref "D4") (pin "9") (pinfunction "DGND_9") (pintype "passive"))
      (node (ref "NT1") (pin "1") (pintype "passive"))
      (node (ref "X4") (pin "2") (pinfunction "2_2") (pintype "passive"))
      (node (ref "X4") (pin "3") (pinfunction "3_3") (pintype "passive"))
      (node (ref "X5") (pin "2") (pinfunction "2_2") (pintype "passive"))
      (node (ref "X5") (pin "3") (pinfunction "3_3") (pintype "passive"))
    )
    (net (code "53") (name "Net-(C50-Pad1)") (class "Default")
      (node (ref "C50") (pin "1") (pinfunction "1_1") (pintype "passive"))
      (node (ref "X4") (pin "1") (pinfunction "1_1") (pintype "passive"))
    )
    (net (code "54") (name "Net-(C51-Pad1)") (class "Default")
      (node (ref "C51") (pin "1") (pinfunction "1_1") (pintype "passive"))
      (node (ref "X4") (pin "4") (pinfunction "4_4") (pintype "passive"))
    )
    (net (code "55") (name "Net-(C55-Pad1)") (class "Default")
      (node (ref "C55") (pin "1") (pinfunction "1_1") (pintype "passive"))
      (node (ref "X5") (pin "1") (pinfunction "1_1") (pintype "passive"))
    )
    (net (code "56") (name "Net-(C56-Pad1)") (class "Default")
      (node (ref "C56") (pin "1") (pinfunction "1_1") (pintype "passive"))
      (node (ref "X5") (pin "4") (pinfunction "4_4") (pintype "passive"))
    )
    (net (code "57") (name "Net-(C61-Pad1)") (class "Default")
      (node (ref "C61") (pin "1") (pinfunction "1_1") (pintype "passive"))
      (node (ref "R37") (pin "1") (pinfunction "1_1") (pintype "passive"))
      (node (ref "R38") (pin "1") (pinfunction "1_1") (pintype "passive"))
    )
    (net (code "58") (name "Net-(C62-Pad1)") (class "Default")
      (node (ref "C62") (pin "1") (pinfunction "1_1") (pintype "passive"))
      (node (ref "R39") (pin "1") (pinfunction "1_1") (pintype "passive"))
      (node (ref "R41") (pin "1") (pinfunction "1_1") (pintype "passive"))
    )
    (net (code "59") (name "Net-(C63-Pad1)") (class "Default")
      (node (ref "C63") (pin "1") (pinfunction "1_1") (pintype "passive"))
      (node (ref "R43") (pin "1") (pinfunction "1_1") (pintype "passive"))
      (node (ref "R44") (pin "1") (pinfunction "1_1") (pintype "passive"))
    )
    (net (code "60") (name "Net-(C64-Pad1)") (class "Default")
      (node (ref "C64") (pin "1") (pinfunction "1_1") (pintype "passive"))
      (node (ref "R49") (pin "1") (pinfunction "1_1") (pintype "passive"))
      (node (ref "R50") (pin "2") (pinfunction "2_2") (pintype "passive"))
    )
    (net (code "61") (name "Net-(C64-Pad2)") (class "Default")
      (node (ref "C64") (pin "2") (pinfunction "2_2") (pintype "passive"))
      (node (ref "R45") (pin "2") (pinfunction "2_2") (pintype "passive"))
      (node (ref "R46") (pin "2") (pinfunction "2_2") (pintype "passive"))
    )
    (net (code "62") (name "Net-(D4A-LINPUT1)") (class "Default")
      (node (ref "C45") (pin "2") (pinfunction "2_2") (pintype "passive"))
      (node (ref "D4") (pin "4") (pinfunction "LINPUT1_4") (pintype "bidirectional"))
    )
    (net (code "63") (name "Net-(D4A-RINPUT1)") (class "Default")
      (node (ref "C49") (pin "2") (pinfunction "2_2") (pintype "passive"))
      (node (ref "D4") (pin "5") (pinfunction "RINPUT1_5") (pintype "bidirectional"))
    )
    (net (code "64") (name "Net-(D4A-VMID)") (class "Default")
      (node (ref "C46") (pin "1") (pinfunction "1_1") (pintype "passive"))
      (node (ref "C47") (pin "1") (pinfunction "1_1") (pintype "passive"))
      (node (ref "D4") (pin "27") (pinfunction "VMID_27") (pintype "passive"))
    )
    (net (code "65") (name "Net-(D4B-SPKVDD1)") (class "Default")
      (node (ref "C38") (pin "1") (pinfunction "1_1") (pintype "passive"))
      (node (ref "C39") (pin "1") (pinfunction "1_1") (pintype "passive"))
      (node (ref "D4") (pin "26") (pinfunction "SPKVDD1_26") (pintype "power_in"))
      (node (ref "L5") (pin "2") (pinfunction "2_2") (pintype "passive"))
    )
    (net (code "66") (name "Net-(D4B-SPKVDD2)") (class "Default")
      (node (ref "C43") (pin "1") (pinfunction "1_1") (pintype "passive"))
      (node (ref "C44") (pin "1") (pinfunction "1_1") (pintype "passive"))
      (node (ref "D4") (pin "21") (pinfunction "SPKVDD2_21") (pintype "power_in"))
      (node (ref "L6") (pin "2") (pinfunction "2_2") (pintype "passive"))
    )
    (net (code "67") (name "Net-(D5A-1OUT)") (class "Default")
      (node (ref "D5") (pin "1") (pinfunction "1OUT_1") (pintype "output"))
      (node (ref "D5") (pin "2") (pinfunction "IN1-_2") (pintype "tri_state"))
      (node (ref "R35") (pin "2") (pinfunction "2_2") (pintype "passive"))
    )
    (net (code "68") (name "Net-(D5A-IN1+)") (class "Default")
      (node (ref "D5") (pin "3") (pinfunction "IN1+_3") (pintype "tri_state"))
      (node (ref "U6") (pin "15") (pinfunction "REF_15") (pintype "input"))
    )
    (net (code "69") (name "Net-(D5B-2OUT)") (class "Default")
      (node (ref "C61") (pin "2") (pinfunction "2_2") (pintype "passive"))
      (node (ref "D5") (pin "6") (pinfunction "IN2-_6") (pintype "tri_state"))
      (node (ref "D5") (pin "7") (pinfunction "2OUT_7") (pintype "output"))
    )
    (net (code "70") (name "Net-(D5B-IN2+)") (class "Default")
      (node (ref "D5") (pin "5") (pinfunction "IN2+_5") (pintype "tri_state"))
      (node (ref "R35") (pin "1") (pinfunction "1_1") (pintype "passive"))
      (node (ref "R36") (pin "2") (pinfunction "2_2") (pintype "passive"))
    )
    (net (code "71") (name "Net-(R40-Pad1)") (class "Default")
      (node (ref "R40") (pin "1") (pinfunction "1_1") (pintype "passive"))
      (node (ref "R41") (pin "2") (pinfunction "2_2") (pintype "passive"))
    )
    (net (code "72") (name "Net-(R42-Pad1)") (class "Default")
      (node (ref "R42") (pin "1") (pinfunction "1_1") (pintype "passive"))
      (node (ref "R43") (pin "2") (pinfunction "2_2") (pintype "passive"))
    )
    (net (code "73") (name "SPKGND") (class "Default")
      (node (ref "C37") (pin "2") (pinfunction "2_2") (pintype "passive"))
      (node (ref "C38") (pin "2") (pinfunction "2_2") (pintype "passive"))
      (node (ref "C39") (pin "2") (pinfunction "2_2") (pintype "passive"))
      (node (ref "C42") (pin "2") (pinfunction "2_2") (pintype "passive"))
      (node (ref "C43") (pin "2") (pinfunction "2_2") (pintype "passive"))
      (node (ref "C44") (pin "2") (pinfunction "2_2") (pintype "passive"))
      (node (ref "D4") (pin "20") (pinfunction "SPKGND2_20") (pintype "passive"))
      (node (ref "D4") (pin "24") (pinfunction "SPKGND1_24") (pintype "passive"))
      (node (ref "NT2") (pin "2") (pintype "passive"))
    )
    (net (code "74") (name "unconnected-(D4A-MICBIAS-Pad1)") (class "Default")
      (node (ref "D4") (pin "1") (pinfunction "MICBIAS_1") (pintype "passive"))
    )
    (net (code "75") (name "unconnected-(D4A-OUT3-Pad30)") (class "Default")
      (node (ref "D4") (pin "30") (pinfunction "OUT3_30") (pintype "output"))
    )
    (net (code "76") (name "unconnected-(D6-IOA0-Pad21)") (class "Default")
      (node (ref "D6") (pin "21") (pinfunction "IOA0_21") (pintype "bidirectional"))
    )
    (net (code "77") (name "unconnected-(D6-IOA1-Pad20)") (class "Default")
      (node (ref "D6") (pin "20") (pinfunction "IOA1_20") (pintype "bidirectional"))
    )
    (net (code "78") (name "unconnected-(D6-IOA2-Pad19)") (class "Default")
      (node (ref "D6") (pin "19") (pinfunction "IOA2_19") (pintype "bidirectional"))
    )
    (net (code "79") (name "unconnected-(D6-IOA3-Pad18)") (class "Default")
      (node (ref "D6") (pin "18") (pinfunction "IOA3_18") (pintype "bidirectional"))
    )
    (net (code "80") (name "unconnected-(D6-IOA4-Pad17)") (class "Default")
      (node (ref "D6") (pin "17") (pinfunction "IOA4_17") (pintype "bidirectional"))
    )
    (net (code "81") (name "unconnected-(D6-IOA5-Pad16)") (class "Default")
      (node (ref "D6") (pin "16") (pinfunction "IOA5_16") (pintype "bidirectional"))
    )
    (net (code "82") (name "unconnected-(D6-IOA6-Pad15)") (class "Default")
      (node (ref "D6") (pin "15") (pinfunction "IOA6_15") (pintype "bidirectional"))
    )
    (net (code "83") (name "unconnected-(D6-IOA7-Pad14)") (class "Default")
      (node (ref "D6") (pin "14") (pinfunction "IOA7_14") (pintype "bidirectional"))
    )
    (net (code "84") (name "unconnected-(D6-IOB0-Pad13)") (class "Default")
      (node (ref "D6") (pin "13") (pinfunction "IOB0_13") (pintype "bidirectional"))
    )
    (net (code "85") (name "unconnected-(D6-IOB1-Pad12)") (class "Default")
      (node (ref "D6") (pin "12") (pinfunction "IOB1_12") (pintype "bidirectional"))
    )
    (net (code "86") (name "unconnected-(D6-IOB2-Pad11)") (class "Default")
      (node (ref "D6") (pin "11") (pinfunction "IOB2_11") (pintype "bidirectional"))
    )
    (net (code "87") (name "unconnected-(D6-IOB3-Pad10)") (class "Default")
      (node (ref "D6") (pin "10") (pinfunction "IOB3_10") (pintype "bidirectional"))
    )
    (net (code "88") (name "unconnected-(D6-IOB4-Pad9)") (class "Default")
      (node (ref "D6") (pin "9") (pinfunction "IOB4_9") (pintype "bidirectional"))
    )
    (net (code "89") (name "unconnected-(D6-IOB5-Pad8)") (class "Default")
      (node (ref "D6") (pin "8") (pinfunction "IOB5_8") (pintype "bidirectional"))
    )
    (net (code "90") (name "unconnected-(D6-IOB6-Pad7)") (class "Default")
      (node (ref "D6") (pin "7") (pinfunction "IOB6_7") (pintype "bidirectional"))
    )
    (net (code "91") (name "unconnected-(D6-IOB7-Pad6)") (class "Default")
      (node (ref "D6") (pin "6") (pinfunction "IOB7_6") (pintype "bidirectional"))
    )
    (net (code "92") (name "unconnected-(D6-TST1-Pad39)") (class "Default")
      (node (ref "D6") (pin "39") (pinfunction "TST1_39") (pintype "passive"))
    )
    (net (code "93") (name "unconnected-(D6-n.c.-Pad2)") (class "Default")
      (node (ref "D6") (pin "2") (pinfunction "n.c._2") (pintype "passive"))
    )
    (net (code "94") (name "unconnected-(D6-n.c.-Pad5)") (class "Default")
      (node (ref "D6") (pin "5") (pinfunction "n.c._5") (pintype "passive"))
    )
    (net (code "95") (name "unconnected-(J5-Pad5)") (class "Default")
      (node (ref "J5") (pin "5") (pinfunction "5_5") (pintype "passive"))
    )
    (net (code "96") (name "unconnected-(J6-Pad4)") (class "Default")
      (node (ref "J6") (pin "4") (pinfunction "4_4") (pintype "passive"))
    )
    (net (code "97") (name "unconnected-(J6-Pad7)") (class "Default")
      (node (ref "J6") (pin "7") (pinfunction "7_7") (pintype "passive"))
    )
    (net (code "98") (name "unconnected-(J6-Pad9)") (class "Default")
      (node (ref "J6") (pin "9") (pinfunction "9_9") (pintype "passive"))
    )
    (net (code "99") (name "unconnected-(J6-Pad11)") (class "Default")
      (node (ref "J6") (pin "11") (pinfunction "11_11") (pintype "passive"))
    )
    (net (code "100") (name "unconnected-(J6-Pad13)") (class "Default")
      (node (ref "J6") (pin "13") (pinfunction "13_13") (pintype "passive"))
    )
    (net (code "101") (name "unconnected-(J6-Pad15)") (class "Default")
      (node (ref "J6") (pin "15") (pinfunction "15_15") (pintype "passive"))
    )
    (net (code "102") (name "unconnected-(J6-Pad17)") (class "Default")
      (node (ref "J6") (pin "17") (pinfunction "17_17") (pintype "passive"))
    )
    (net (code "103") (name "unconnected-(J6-Pad19)") (class "Default")
      (node (ref "J6") (pin "19") (pinfunction "19_19") (pintype "passive"))
    )
    (net (code "104") (name "unconnected-(J6-Pad21)") (class "Default")
      (node (ref "J6") (pin "21") (pinfunction "21_21") (pintype "passive"))
    )
    (net (code "105") (name "unconnected-(J6-Pad23)") (class "Default")
      (node (ref "J6") (pin "23") (pinfunction "23_23") (pintype "passive"))
    )
    (net (code "106") (name "unconnected-(J6-Pad25)") (class "Default")
      (node (ref "J6") (pin "25") (pinfunction "25_25") (pintype "passive"))
    )
    (net (code "107") (name "unconnected-(J6-Pad27)") (class "Default")
      (node (ref "J6") (pin "27") (pinfunction "27_27") (pintype "passive"))
    )
    (net (code "108") (name "unconnected-(J6-Pad29)") (class "Default")
      (node (ref "J6") (pin "29") (pinfunction "29_29") (pintype "passive"))
    )
    (net (code "109") (name "unconnected-(J6-Pad31)") (class "Default")
      (node (ref "J6") (pin "31") (pinfunction "31_31") (pintype "passive"))
    )
    (net (code "110") (name "unconnected-(J6-Pad33)") (class "Default")
      (node (ref "J6") (pin "33") (pinfunction "33_33") (pintype "passive"))
    )
    (net (code "111") (name "unconnected-(J6-Pad35)") (class "Default")
      (node (ref "J6") (pin "35") (pinfunction "35_35") (pintype "passive"))
    )
    (net (code "112") (name "unconnected-(J6-Pad37)") (class "Default")
      (node (ref "J6") (pin "37") (pinfunction "37_37") (pintype "passive"))
    )
    (net (code "113") (name "unconnected-(J6-Pad39)") (class "Default")
      (node (ref "J6") (pin "39") (pinfunction "39_39") (pintype "passive"))
    )
    (net (code "114") (name "unconnected-(J6-Pad40)") (class "Default")
      (node (ref "J6") (pin "40") (pinfunction "40_40") (pintype "passive"))
    )
    (net (code "115") (name "unconnected-(P2-Pad3)") (class "Default")
      (node (ref "P2") (pin "3") (pinfunction "3_3") (pintype "passive"))
    )
    (net (code "116") (name "unconnected-(P2-Pad4)") (class "Default")
      (node (ref "P2") (pin "4") (pinfunction "4_4") (pintype "passive"))
    )
    (net (code "117") (name "unconnected-(P2-Pad6)") (class "Default")
      (node (ref "P2") (pin "6") (pinfunction "6_6") (pintype "passive"))
    )
    (net (code "118") (name "unconnected-(P2-Pad7)") (class "Default")
      (node (ref "P2") (pin "7") (pinfunction "7_7") (pintype "passive"))
    )
    (net (code "119") (name "unconnected-(P2-Pad8)") (class "Default")
      (node (ref "P2") (pin "8") (pinfunction "8_8") (pintype "passive"))
    )
    (net (code "120") (name "unconnected-(P2-Pad10)") (class "Default")
      (node (ref "P2") (pin "10") (pinfunction "10_10") (pintype "passive"))
    )
    (net (code "121") (name "unconnected-(U6-RFB-Pad16)") (class "Default")
      (node (ref "U6") (pin "16") (pinfunction "RFB_16") (pintype "input"))
    )
  )
)
